# sensor.net
KiCad netlist of a schematic drawn in EAGLE
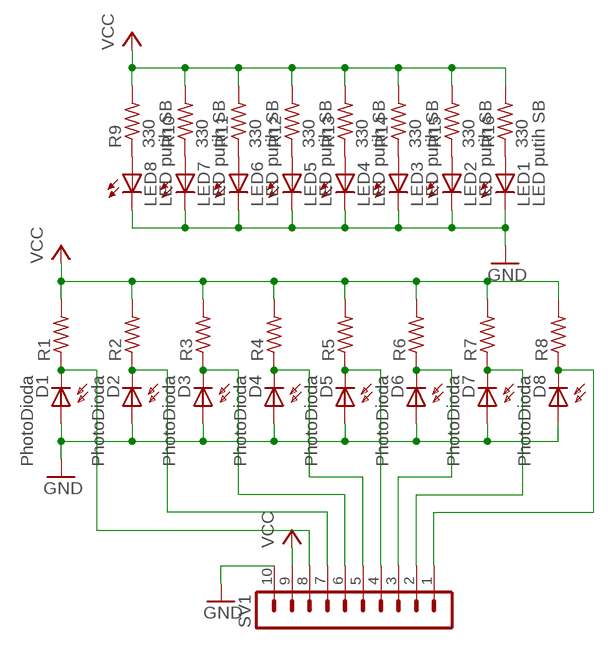
[diagram p0: schematic, sheet 1]

(export (version "E")
  (design (tool "Eeschema 10.0.6"))
  (components
    (comp (ref "D1")
      (value "PhotoDioda")
      (footprint "eagle-import:SFH225")
      (libsource (lib "eagle-import") (part "SFH225"))
    )
    (comp (ref "D2")
      (value "PhotoDioda")
      (footprint "eagle-import:SFH225")
      (libsource (lib "eagle-import") (part "SFH225"))
    )
    (comp (ref "D3")
      (value "PhotoDioda")
      (footprint "eagle-import:SFH225")
      (libsource (lib "eagle-import") (part "SFH225"))
    )
    (comp (ref "D4")
      (value "PhotoDioda")
      (footprint "eagle-import:SFH225")
      (libsource (lib "eagle-import") (part "SFH225"))
    )
    (comp (ref "D5")
      (value "PhotoDioda")
      (footprint "eagle-import:SFH225")
      (libsource (lib "eagle-import") (part "SFH225"))
    )
    (comp (ref "D6")
      (value "PhotoDioda")
      (footprint "eagle-import:SFH225")
      (libsource (lib "eagle-import") (part "SFH225"))
    )
    (comp (ref "D7")
      (value "PhotoDioda")
      (footprint "eagle-import:SFH225")
      (libsource (lib "eagle-import") (part "SFH225"))
    )
    (comp (ref "D8")
      (value "PhotoDioda")
      (footprint "eagle-import:SFH225")
      (libsource (lib "eagle-import") (part "SFH225"))
    )
    (comp (ref "LED1")
      (value "LED putih SB")
      (footprint "eagle-import:LED5MM")
      (libsource (lib "eagle-import") (part "LED5MM"))
    )
    (comp (ref "LED2")
      (value "LED putih SB")
      (footprint "eagle-import:LED5MM")
      (libsource (lib "eagle-import") (part "LED5MM"))
    )
    (comp (ref "LED3")
      (value "LED putih SB")
      (footprint "eagle-import:LED5MM")
      (libsource (lib "eagle-import") (part "LED5MM"))
    )
    (comp (ref "LED4")
      (value "LED putih SB")
      (footprint "eagle-import:LED5MM")
      (libsource (lib "eagle-import") (part "LED5MM"))
    )
    (comp (ref "LED5")
      (value "LED putih SB")
      (footprint "eagle-import:LED5MM")
      (libsource (lib "eagle-import") (part "LED5MM"))
    )
    (comp (ref "LED6")
      (value "LED putih SB")
      (footprint "eagle-import:LED5MM")
      (libsource (lib "eagle-import") (part "LED5MM"))
    )
    (comp (ref "LED7")
      (value "LED putih SB")
      (footprint "eagle-import:LED5MM")
      (libsource (lib "eagle-import") (part "LED5MM"))
    )
    (comp (ref "LED8")
      (value "LED putih SB")
      (footprint "eagle-import:LED5MM")
      (libsource (lib "eagle-import") (part "LED5MM"))
    )
    (comp (ref "R1")
      (value "R-US_0207/10")
      (footprint "eagle-import:0207_10")
      (libsource (lib "eagle-import") (part "R-US_0207/10"))
    )
    (comp (ref "R2")
      (value "R-US_0207/10")
      (footprint "eagle-import:0207_10")
      (libsource (lib "eagle-import") (part "R-US_0207/10"))
    )
    (comp (ref "R3")
      (value "R-US_0207/10")
      (footprint "eagle-import:0207_10")
      (libsource (lib "eagle-import") (part "R-US_0207/10"))
    )
    (comp (ref "R4")
      (value "R-US_0207/10")
      (footprint "eagle-import:0207_10")
      (libsource (lib "eagle-import") (part "R-US_0207/10"))
    )
    (comp (ref "R5")
      (value "R-US_0207/10")
      (footprint "eagle-import:0207_10")
      (libsource (lib "eagle-import") (part "R-US_0207/10"))
    )
    (comp (ref "R6")
      (value "R-US_0207/10")
      (footprint "eagle-import:0207_10")
      (libsource (lib "eagle-import") (part "R-US_0207/10"))
    )
    (comp (ref "R7")
      (value "R-US_0207/10")
      (footprint "eagle-import:0207_10")
      (libsource (lib "eagle-import") (part "R-US_0207/10"))
    )
    (comp (ref "R8")
      (value "R-US_0207/10")
      (footprint "eagle-import:0207_10")
      (libsource (lib "eagle-import") (part "R-US_0207/10"))
    )
    (comp (ref "R9")
      (value "330")
      (footprint "eagle-import:0207_10")
      (libsource (lib "eagle-import") (part "R-US_0207/10"))
    )
    (comp (ref "R10")
      (value "330")
      (footprint "eagle-import:0207_10")
      (libsource (lib "eagle-import") (part "R-US_0207/10"))
    )
    (comp (ref "R11")
      (value "330")
      (footprint "eagle-import:0207_10")
      (libsource (lib "eagle-import") (part "R-US_0207/10"))
    )
    (comp (ref "R12")
      (value "330")
      (footprint "eagle-import:0207_10")
      (libsource (lib "eagle-import") (part "R-US_0207/10"))
    )
    (comp (ref "R13")
      (value "330")
      (footprint "eagle-import:0207_10")
      (libsource (lib "eagle-import") (part "R-US_0207/10"))
    )
    (comp (ref "R14")
      (value "330")
      (footprint "eagle-import:0207_10")
      (libsource (lib "eagle-import") (part "R-US_0207/10"))
    )
    (comp (ref "R15")
      (value "330")
      (footprint "eagle-import:0207_10")
      (libsource (lib "eagle-import") (part "R-US_0207/10"))
    )
    (comp (ref "R16")
      (value "330")
      (footprint "eagle-import:0207_10")
      (libsource (lib "eagle-import") (part "R-US_0207/10"))
    )
    (comp (ref "SV1")
      (value "MA10-1")
      (footprint "eagle-import:MA10-1")
      (libsource (lib "eagle-import") (part "MA10-1"))
    )
  )
  (nets
    (net (code "1") (name "GND") (class "Default")
      (node (ref "D1") (pin "A") (pinfunction "A_A") (pintype "passive"))
      (node (ref "D2") (pin "A") (pinfunction "A_A") (pintype "passive"))
      (node (ref "D3") (pin "A") (pinfunction "A_A") (pintype "passive"))
      (node (ref "D4") (pin "A") (pinfunction "A_A") (pintype "passive"))
      (node (ref "D5") (pin "A") (pinfunction "A_A") (pintype "passive"))
      (node (ref "D6") (pin "A") (pinfunction "A_A") (pintype "passive"))
      (node (ref "D7") (pin "A") (pinfunction "A_A") (pintype "passive"))
      (node (ref "D8") (pin "A") (pinfunction "A_A") (pintype "passive"))
      (node (ref "LED1") (pin "K") (pinfunction "C_K") (pintype "passive"))
      (node (ref "LED2") (pin "K") (pinfunction "C_K") (pintype "passive"))
      (node (ref "LED3") (pin "K") (pinfunction "C_K") (pintype "passive"))
      (node (ref "LED4") (pin "K") (pinfunction "C_K") (pintype "passive"))
      (node (ref "LED5") (pin "K") (pinfunction "C_K") (pintype "passive"))
      (node (ref "LED6") (pin "K") (pinfunction "C_K") (pintype "passive"))
      (node (ref "LED7") (pin "K") (pinfunction "C_K") (pintype "passive"))
      (node (ref "LED8") (pin "K") (pinfunction "C_K") (pintype "passive"))
      (node (ref "SV1") (pin "10") (pinfunction "10_10") (pintype "passive"))
    )
    (net (code "2") (name "Net-(D1-C)") (class "Default")
      (node (ref "D1") (pin "K") (pinfunction "C_K") (pintype "passive"))
      (node (ref "R1") (pin "1") (pinfunction "1_1") (pintype "passive"))
      (node (ref "SV1") (pin "8") (pinfunction "8_8") (pintype "passive"))
    )
    (net (code "3") (name "Net-(D2-C)") (class "Default")
      (node (ref "D2") (pin "K") (pinfunction "C_K") (pintype "passive"))
      (node (ref "R2") (pin "1") (pinfunction "1_1") (pintype "passive"))
      (node (ref "SV1") (pin "7") (pinfunction "7_7") (pintype "passive"))
    )
    (net (code "4") (name "Net-(D3-C)") (class "Default")
      (node (ref "D3") (pin "K") (pinfunction "C_K") (pintype "passive"))
      (node (ref "R3") (pin "1") (pinfunction "1_1") (pintype "passive"))
      (node (ref "SV1") (pin "6") (pinfunction "6_6") (pintype "passive"))
    )
    (net (code "5") (name "Net-(D4-C)") (class "Default")
      (node (ref "D4") (pin "K") (pinfunction "C_K") (pintype "passive"))
      (node (ref "R4") (pin "1") (pinfunction "1_1") (pintype "passive"))
      (node (ref "SV1") (pin "5") (pinfunction "5_5") (pintype "passive"))
    )
    (net (code "6") (name "Net-(D5-C)") (class "Default")
      (node (ref "D5") (pin "K") (pinfunction "C_K") (pintype "passive"))
      (node (ref "R5") (pin "1") (pinfunction "1_1") (pintype "passive"))
      (node (ref "SV1") (pin "4") (pinfunction "4_4") (pintype "passive"))
    )
    (net (code "7") (name "Net-(D6-C)") (class "Default")
      (node (ref "D6") (pin "K") (pinfunction "C_K") (pintype "passive"))
      (node (ref "R6") (pin "1") (pinfunction "1_1") (pintype "passive"))
      (node (ref "SV1") (pin "3") (pinfunction "3_3") (pintype "passive"))
    )
    (net (code "8") (name "Net-(D7-C)") (class "Default")
      (node (ref "D7") (pin "K") (pinfunction "C_K") (pintype "passive"))
      (node (ref "R7") (pin "1") (pinfunction "1_1") (pintype "passive"))
      (node (ref "SV1") (pin "2") (pinfunction "2_2") (pintype "passive"))
    )
    (net (code "9") (name "Net-(D8-C)") (class "Default")
      (node (ref "D8") (pin "K") (pinfunction "C_K") (pintype "passive"))
      (node (ref "R8") (pin "1") (pinfunction "1_1") (pintype "passive"))
      (node (ref "SV1") (pin "1") (pinfunction "1_1") (pintype "passive"))
    )
    (net (code "10") (name "Net-(LED1-PadA)") (class "Default")
      (node (ref "LED1") (pin "A") (pinfunction "A_A") (pintype "passive"))
      (node (ref "R16") (pin "1") (pinfunction "1_1") (pintype "passive"))
    )
    (net (code "11") (name "Net-(LED2-PadA)") (class "Default")
      (node (ref "LED2") (pin "A") (pinfunction "A_A") (pintype "passive"))
      (node (ref "R15") (pin "1") (pinfunction "1_1") (pintype "passive"))
    )
    (net (code "12") (name "Net-(LED3-PadA)") (class "Default")
      (node (ref "LED3") (pin "A") (pinfunction "A_A") (pintype "passive"))
      (node (ref "R14") (pin "1") (pinfunction "1_1") (pintype "passive"))
    )
    (net (code "13") (name "Net-(LED4-PadA)") (class "Default")
      (node (ref "LED4") (pin "A") (pinfunction "A_A") (pintype "passive"))
      (node (ref "R13") (pin "1") (pinfunction "1_1") (pintype "passive"))
    )
    (net (code "14") (name "Net-(LED5-PadA)") (class "Default")
      (node (ref "LED5") (pin "A") (pinfunction "A_A") (pintype "passive"))
      (node (ref "R12") (pin "1") (pinfunction "1_1") (pintype "passive"))
    )
    (net (code "15") (name "Net-(LED6-PadA)") (class "Default")
      (node (ref "LED6") (pin "A") (pinfunction "A_A") (pintype "passive"))
      (node (ref "R11") (pin "1") (pinfunction "1_1") (pintype "passive"))
    )
    (net (code "16") (name "Net-(LED7-PadA)") (class "Default")
      (node (ref "LED7") (pin "A") (pinfunction "A_A") (pintype "passive"))
      (node (ref "R10") (pin "1") (pinfunction "1_1") (pintype "passive"))
    )
    (net (code "17") (name "Net-(LED8-PadA)") (class "Default")
      (node (ref "LED8") (pin "A") (pinfunction "A_A") (pintype "passive"))
      (node (ref "R9") (pin "1") (pinfunction "1_1") (pintype "passive"))
    )
    (net (code "18") (name "VCC") (class "Default")
      (node (ref "R1") (pin "2") (pinfunction "2_2") (pintype "passive"))
      (node (ref "R10") (pin "2") (pinfunction "2_2") (pintype "passive"))
      (node (ref "R11") (pin "2") (pinfunction "2_2") (pintype "passive"))
      (node (ref "R12") (pin "2") (pinfunction "2_2") (pintype "passive"))
      (node (ref "R13") (pin "2") (pinfunction "2_2") (pintype "passive"))
      (node (ref "R14") (pin "2") (pinfunction "2_2") (pintype "passive"))
      (node (ref "R15") (pin "2") (pinfunction "2_2") (pintype "passive"))
      (node (ref "R16") (pin "2") (pinfunction "2_2") (pintype "passive"))
      (node (ref "R2") (pin "2") (pinfunction "2_2") (pintype "passive"))
      (node (ref "R3") (pin "2") (pinfunction "2_2") (pintype "passive"))
      (node (ref "R4") (pin "2") (pinfunction "2_2") (pintype "passive"))
      (node (ref "R5") (pin "2") (pinfunction "2_2") (pintype "passive"))
      (node (ref "R6") (pin "2") (pinfunction "2_2") (pintype "passive"))
      (node (ref "R7") (pin "2") (pinfunction "2_2") (pintype "passive"))
      (node (ref "R8") (pin "2") (pinfunction "2_2") (pintype "passive"))
      (node (ref "R9") (pin "2") (pinfunction "2_2") (pintype "passive"))
      (node (ref "SV1") (pin "9") (pinfunction "9_9") (pintype "passive"))
    )
  )
)
